# robot.net
KiCad netlist of a schematic drawn in EAGLE
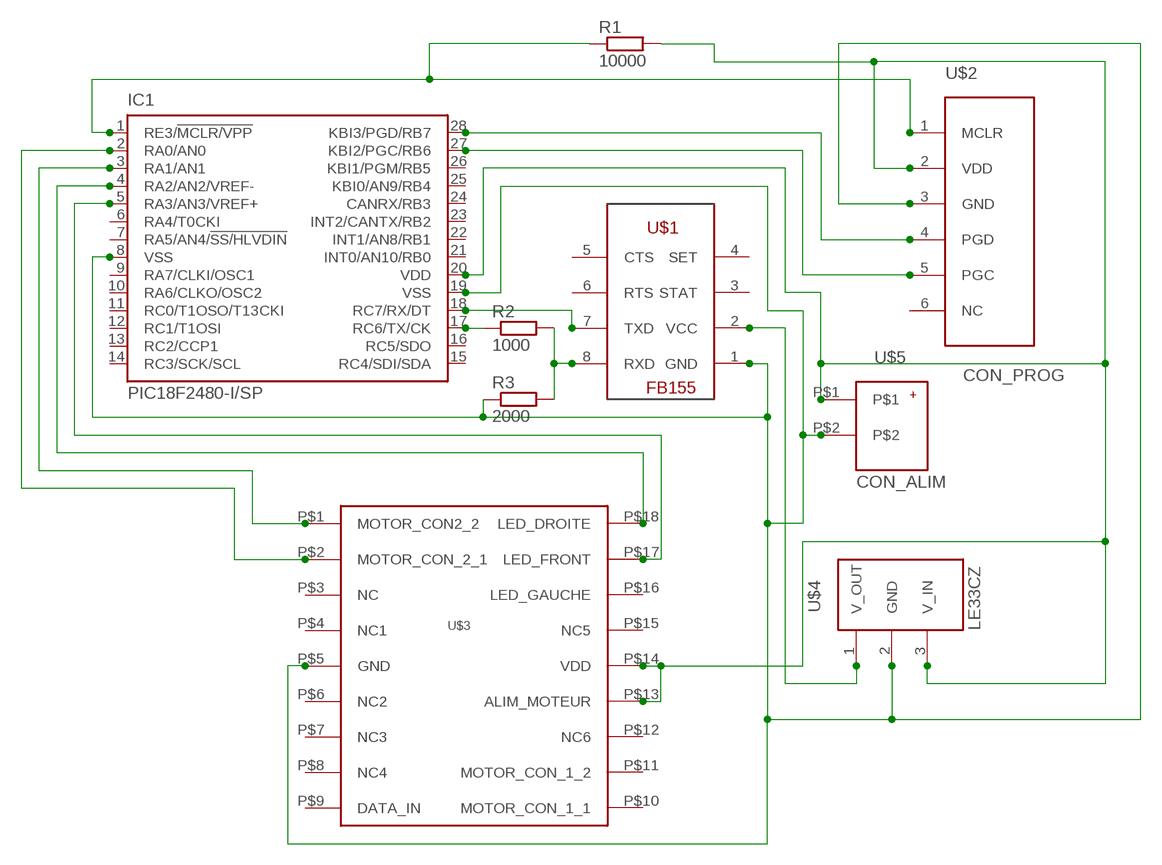
[diagram p0: schematic, sheet 1]

(export (version "E")
  (design (tool "Eeschema 10.0.6"))
  (components
    (comp (ref "IC1")
      (value "PIC18F2480-I/SP")
      (footprint "eagle-import:DIL28-3")
      (fields (field (name "MF") "MICROCHIP"))
      (libsource (lib "eagle-import") (part "PIC18F280-I/SP4"))
    )
    (comp (ref "R1")
      (value "10000")
      (footprint "eagle-import:0207_7")
      (libsource (lib "eagle-import") (part "R-EU_0207/7"))
    )
    (comp (ref "R2")
      (value "1000")
      (footprint "eagle-import:0207_7")
      (libsource (lib "eagle-import") (part "R-EU_0207/7"))
    )
    (comp (ref "R3")
      (value "2000")
      (footprint "eagle-import:0207_7")
      (libsource (lib "eagle-import") (part "R-EU_0207/7"))
    )
    (comp (ref "U$1")
      (value "FB155")
      (footprint "eagle-import:DIL8L")
      (libsource (lib "eagle-import") (part "FB155"))
    )
    (comp (ref "U$2")
      (value "CON_PROG")
      (footprint "eagle-import:CON_PROG")
      (libsource (lib "eagle-import") (part "CON_PROG"))
    )
    (comp (ref "U$3")
      (value "ROBOT")
      (footprint "eagle-import:CON_ROBOT")
      (libsource (lib "eagle-import") (part "ROBOT"))
    )
    (comp (ref "U$4")
      (value "LE33CZ")
      (footprint "eagle-import:T092")
      (libsource (lib "eagle-import") (part "LE33CZ"))
    )
    (comp (ref "U$5")
      (value "CON_ALIM")
      (footprint "eagle-import:CON_ALIM")
      (libsource (lib "eagle-import") (part "CON_ALIM"))
    )
  )
  (nets
    (net (code "1") (name "Net-(IC1-KBI2{slash}PGC{slash}RB6)") (class "Default")
      (node (ref "IC1") (pin "27") (pinfunction "KBI2/PGC/RB6_27") (pintype "bidirectional"))
      (node (ref "U$2") (pin "5") (pinfunction "PGC_5") (pintype "bidirectional"))
    )
    (net (code "2") (name "Net-(IC1-KBI3{slash}PGD{slash}RB7)") (class "Default")
      (node (ref "IC1") (pin "28") (pinfunction "KBI3/PGD/RB7_28") (pintype "bidirectional"))
      (node (ref "U$2") (pin "4") (pinfunction "PGD_4") (pintype "bidirectional"))
    )
    (net (code "3") (name "Net-(IC1-RA0{slash}AN0)") (class "Default")
      (node (ref "IC1") (pin "2") (pinfunction "RA0/AN0_2") (pintype "bidirectional"))
      (node (ref "U$3") (pin "P$2") (pinfunction "MOTOR_CON_2_1_P$2") (pintype "output"))
    )
    (net (code "4") (name "Net-(IC1-RA1{slash}AN1)") (class "Default")
      (node (ref "IC1") (pin "3") (pinfunction "RA1/AN1_3") (pintype "bidirectional"))
      (node (ref "U$3") (pin "P$1") (pinfunction "MOTOR_CON2_2_P$1") (pintype "output"))
    )
    (net (code "5") (name "Net-(IC1-RA2{slash}AN2{slash}VREF-)") (class "Default")
      (node (ref "IC1") (pin "4") (pinfunction "RA2/AN2/VREF-_4") (pintype "bidirectional"))
      (node (ref "U$3") (pin "P$18") (pinfunction "LED_DROITE_P$18") (pintype "output"))
    )
    (net (code "6") (name "Net-(IC1-RA3{slash}AN3{slash}VREF+)") (class "Default")
      (node (ref "IC1") (pin "5") (pinfunction "RA3/AN3/VREF+_5") (pintype "bidirectional"))
      (node (ref "U$3") (pin "P$17") (pinfunction "LED_FRONT_P$17") (pintype "output"))
    )
    (net (code "7") (name "Net-(IC1-RC6{slash}TX{slash}CK)") (class "Default")
      (node (ref "IC1") (pin "17") (pinfunction "RC6/TX/CK_17") (pintype "bidirectional"))
      (node (ref "R2") (pin "1") (pinfunction "1_1") (pintype "passive"))
    )
    (net (code "8") (name "Net-(IC1-RC7{slash}RX{slash}DT)") (class "Default")
      (node (ref "IC1") (pin "18") (pinfunction "RC7/RX/DT_18") (pintype "bidirectional"))
      (node (ref "U$1") (pin "7") (pinfunction "TXD_7") (pintype "output"))
    )
    (net (code "9") (name "Net-(IC1-RE3{slash}~{MCLR{slash}VPP})") (class "Default")
      (node (ref "IC1") (pin "1") (pinfunction "RE3/~{MCLR/VPP}_1") (pintype "input"))
      (node (ref "R1") (pin "1") (pinfunction "1_1") (pintype "passive"))
      (node (ref "U$2") (pin "1") (pinfunction "MCLR_1") (pintype "bidirectional"))
    )
    (net (code "10") (name "Net-(IC1-VDD)") (class "Default")
      (node (ref "IC1") (pin "20") (pinfunction "VDD_20") (pintype "power_in"))
      (node (ref "R1") (pin "2") (pinfunction "2_2") (pintype "passive"))
      (node (ref "U$2") (pin "2") (pinfunction "VDD_2") (pintype "bidirectional"))
      (node (ref "U$3") (pin "P$13") (pinfunction "ALIM_MOTEUR_P$13") (pintype "power_in"))
      (node (ref "U$3") (pin "P$14") (pinfunction "VDD_P$14") (pintype "power_in"))
      (node (ref "U$4") (pin "3") (pinfunction "V_IN_3") (pintype "bidirectional"))
      (node (ref "U$5") (pin "P$1") (pinfunction "P$1_P$1") (pintype "bidirectional"))
    )
    (net (code "11") (name "Net-(U$1-GND)") (class "Default")
      (node (ref "IC1") (pin "19") (pinfunction "VSS_19") (pintype "power_in"))
      (node (ref "IC1") (pin "8") (pinfunction "VSS_8") (pintype "power_in"))
      (node (ref "R3") (pin "1") (pinfunction "1_1") (pintype "passive"))
      (node (ref "U$1") (pin "1") (pinfunction "GND_1") (pintype "power_in"))
      (node (ref "U$2") (pin "3") (pinfunction "GND_3") (pintype "bidirectional"))
      (node (ref "U$3") (pin "P$5") (pinfunction "GND_P$5") (pintype "power_in"))
      (node (ref "U$4") (pin "2") (pinfunction "GND_2") (pintype "bidirectional"))
      (node (ref "U$5") (pin "P$2") (pinfunction "P$2_P$2") (pintype "bidirectional"))
    )
    (net (code "12") (name "Net-(U$1-RXD)") (class "Default")
      (node (ref "R2") (pin "2") (pinfunction "2_2") (pintype "passive"))
      (node (ref "R3") (pin "2") (pinfunction "2_2") (pintype "passive"))
      (node (ref "U$1") (pin "8") (pinfunction "RXD_8") (pintype "input"))
    )
    (net (code "13") (name "Net-(U$1-VCC)") (class "Default")
      (node (ref "U$1") (pin "2") (pinfunction "VCC_2") (pintype "power_in"))
      (node (ref "U$4") (pin "1") (pinfunction "V_OUT_1") (pintype "bidirectional"))
    )
    (net (code "14") (name "unconnected-(IC1-CANRX{slash}RB3-Pad24)") (class "Default")
      (node (ref "IC1") (pin "24") (pinfunction "CANRX/RB3_24") (pintype "bidirectional"))
    )
    (net (code "15") (name "unconnected-(IC1-INT0{slash}AN10{slash}RB0-Pad21)") (class "Default")
      (node (ref "IC1") (pin "21") (pinfunction "INT0/AN10/RB0_21") (pintype "bidirectional"))
    )
    (net (code "16") (name "unconnected-(IC1-INT1{slash}AN8{slash}RB1-Pad22)") (class "Default")
      (node (ref "IC1") (pin "22") (pinfunction "INT1/AN8/RB1_22") (pintype "bidirectional"))
    )
    (net (code "17") (name "unconnected-(IC1-INT2{slash}CANTX{slash}RB2-Pad23)") (class "Default")
      (node (ref "IC1") (pin "23") (pinfunction "INT2/CANTX/RB2_23") (pintype "bidirectional"))
    )
    (net (code "18") (name "unconnected-(IC1-KBI0{slash}AN9{slash}RB4-Pad25)") (class "Default")
      (node (ref "IC1") (pin "25") (pinfunction "KBI0/AN9/RB4_25") (pintype "bidirectional"))
    )
    (net (code "19") (name "unconnected-(IC1-KBI1{slash}PGM{slash}RB5-Pad26)") (class "Default")
      (node (ref "IC1") (pin "26") (pinfunction "KBI1/PGM/RB5_26") (pintype "bidirectional"))
    )
    (net (code "20") (name "unconnected-(IC1-RA4{slash}T0CKI-Pad6)") (class "Default")
      (node (ref "IC1") (pin "6") (pinfunction "RA4/T0CKI_6") (pintype "bidirectional"))
    )
    (net (code "21") (name "unconnected-(IC1-RA5{slash}AN4{slash}~{SS{slash}HLVDIN}-Pad7)") (class "Default")
      (node (ref "IC1") (pin "7") (pinfunction "RA5/AN4/~{SS/HLVDIN}_7") (pintype "bidirectional"))
    )
    (net (code "22") (name "unconnected-(IC1-RA6{slash}CLKO{slash}OSC2-Pad10)") (class "Default")
      (node (ref "IC1") (pin "10") (pinfunction "RA6/CLKO/OSC2_10") (pintype "output"))
    )
    (net (code "23") (name "unconnected-(IC1-RA7{slash}CLKI{slash}OSC1-Pad9)") (class "Default")
      (node (ref "IC1") (pin "9") (pinfunction "RA7/CLKI/OSC1_9") (pintype "input"))
    )
    (net (code "24") (name "unconnected-(IC1-RC0{slash}T1OSO{slash}T13CKI-Pad11)") (class "Default")
      (node (ref "IC1") (pin "11") (pinfunction "RC0/T1OSO/T13CKI_11") (pintype "bidirectional"))
    )
    (net (code "25") (name "unconnected-(IC1-RC1{slash}T1OSI-Pad12)") (class "Default")
      (node (ref "IC1") (pin "12") (pinfunction "RC1/T1OSI_12") (pintype "bidirectional"))
    )
    (net (code "26") (name "unconnected-(IC1-RC2{slash}CCP1-Pad13)") (class "Default")
      (node (ref "IC1") (pin "13") (pinfunction "RC2/CCP1_13") (pintype "bidirectional"))
    )
    (net (code "27") (name "unconnected-(IC1-RC3{slash}SCK{slash}SCL-Pad14)") (class "Default")
      (node (ref "IC1") (pin "14") (pinfunction "RC3/SCK/SCL_14") (pintype "bidirectional"))
    )
    (net (code "28") (name "unconnected-(IC1-RC4{slash}SDI{slash}SDA-Pad15)") (class "Default")
      (node (ref "IC1") (pin "15") (pinfunction "RC4/SDI/SDA_15") (pintype "bidirectional"))
    )
    (net (code "29") (name "unconnected-(IC1-RC5{slash}SDO-Pad16)") (class "Default")
      (node (ref "IC1") (pin "16") (pinfunction "RC5/SDO_16") (pintype "bidirectional"))
    )
    (net (code "30") (name "unconnected-(U$1-CTS-Pad5)") (class "Default")
      (node (ref "U$1") (pin "5") (pinfunction "CTS_5") (pintype "input"))
    )
    (net (code "31") (name "unconnected-(U$1-RTS-Pad6)") (class "Default")
      (node (ref "U$1") (pin "6") (pinfunction "RTS_6") (pintype "output"))
    )
    (net (code "32") (name "unconnected-(U$1-SET-Pad4)") (class "Default")
      (node (ref "U$1") (pin "4") (pinfunction "SET_4") (pintype "input"))
    )
    (net (code "33") (name "unconnected-(U$1-STAT-Pad3)") (class "Default")
      (node (ref "U$1") (pin "3") (pinfunction "STAT_3") (pintype "output"))
    )
    (net (code "34") (name "unconnected-(U$2-NC-Pad6)") (class "Default")
      (node (ref "U$2") (pin "6") (pinfunction "NC_6") (pintype "bidirectional"))
    )
    (net (code "35") (name "unconnected-(U$3-DATA_IN-PadP$9)") (class "Default")
      (node (ref "U$3") (pin "P$9") (pinfunction "DATA_IN_P$9") (pintype "input"))
    )
    (net (code "36") (name "unconnected-(U$3-LED_GAUCHE-PadP$16)") (class "Default")
      (node (ref "U$3") (pin "P$16") (pinfunction "LED_GAUCHE_P$16") (pintype "output"))
    )
    (net (code "37") (name "unconnected-(U$3-MOTOR_CON_1_1-PadP$10)") (class "Default")
      (node (ref "U$3") (pin "P$10") (pinfunction "MOTOR_CON_1_1_P$10") (pintype "output"))
    )
    (net (code "38") (name "unconnected-(U$3-MOTOR_CON_1_2-PadP$11)") (class "Default")
      (node (ref "U$3") (pin "P$11") (pinfunction "MOTOR_CON_1_2_P$11") (pintype "output"))
    )
    (net (code "39") (name "unconnected-(U$3-NC-PadP$3)") (class "Default")
      (node (ref "U$3") (pin "P$3") (pinfunction "NC_P$3") (pintype "no_connect"))
    )
    (net (code "40") (name "unconnected-(U$3-NC1-PadP$4)") (class "Default")
      (node (ref "U$3") (pin "P$4") (pinfunction "NC1_P$4") (pintype "no_connect"))
    )
    (net (code "41") (name "unconnected-(U$3-NC2-PadP$6)") (class "Default")
      (node (ref "U$3") (pin "P$6") (pinfunction "NC2_P$6") (pintype "no_connect"))
    )
    (net (code "42") (name "unconnected-(U$3-NC3-PadP$7)") (class "Default")
      (node (ref "U$3") (pin "P$7") (pinfunction "NC3_P$7") (pintype "no_connect"))
    )
    (net (code "43") (name "unconnected-(U$3-NC4-PadP$8)") (class "Default")
      (node (ref "U$3") (pin "P$8") (pinfunction "NC4_P$8") (pintype "no_connect"))
    )
    (net (code "44") (name "unconnected-(U$3-NC5-PadP$15)") (class "Default")
      (node (ref "U$3") (pin "P$15") (pinfunction "NC5_P$15") (pintype "no_connect"))
    )
    (net (code "45") (name "unconnected-(U$3-NC6-PadP$12)") (class "Default")
      (node (ref "U$3") (pin "P$12") (pinfunction "NC6_P$12") (pintype "no_connect"))
    )
  )
)
